# Main.net
KiCad netlist of a schematic drawn in Altium Designer
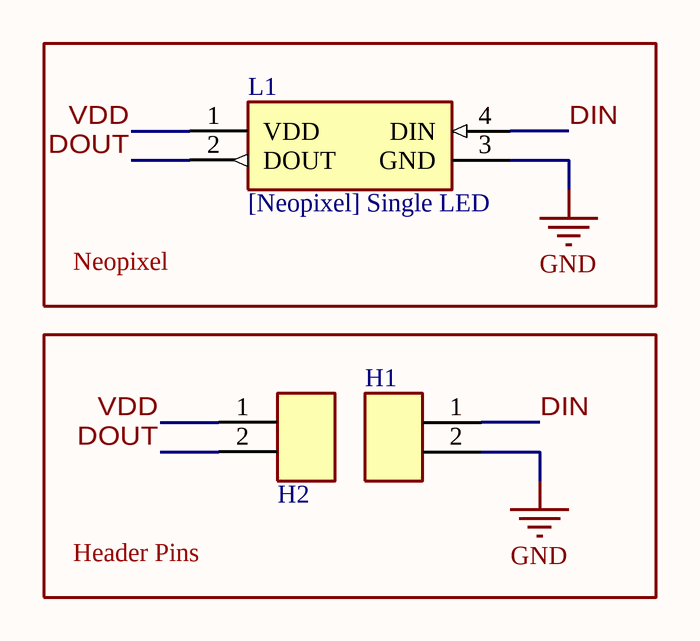
[diagram p0: Main.SchDoc]

(export (version "E")
  (design (tool "Eeschema 10.0.6"))
  (components
    (comp (ref "H1")
      (value "1x2 Header")
      (footprint "[Header] 1x2 Male")
      (description "2.54mm pitch")
      (libsource (lib "Connectors") (part "[Header] 1x2 Male"))
    )
    (comp (ref "H2")
      (value "1x2 Header")
      (footprint "[Header] 1x2 Male")
      (description "2.54mm pitch")
      (libsource (lib "") (part "[Header] 1x2 Male_1"))
    )
    (comp (ref "L1")
      (value "[Neopixel] Single LED")
      (footprint "[Neopixel] Single LED")
      (description "WS2812B")
      (libsource (lib "LEDs") (part "[Neopixel] Single LED"))
    )
  )
  (nets
    (net (code "1") (name "/DIN") (class "Default")
      (node (ref "H1") (pin "1") (pintype "passive"))
      (node (ref "L1") (pin "4") (pinfunction "DIN_4") (pintype "input"))
    )
    (net (code "2") (name "/DOUT") (class "Default")
      (node (ref "H2") (pin "2") (pintype "passive"))
      (node (ref "L1") (pin "2") (pinfunction "DOUT_2") (pintype "output"))
    )
    (net (code "3") (name "/VDD") (class "Default")
      (node (ref "H2") (pin "1") (pintype "passive"))
      (node (ref "L1") (pin "1") (pinfunction "VDD_1") (pintype "power_in"))
    )
    (net (code "4") (name "GND") (class "Default")
      (node (ref "H1") (pin "2") (pintype "passive"))
      (node (ref "L1") (pin "3") (pinfunction "GND_3") (pintype "power_in"))
    )
  )
)
